# LCD_Button.net
KiCad netlist of a schematic drawn in Altium Designer
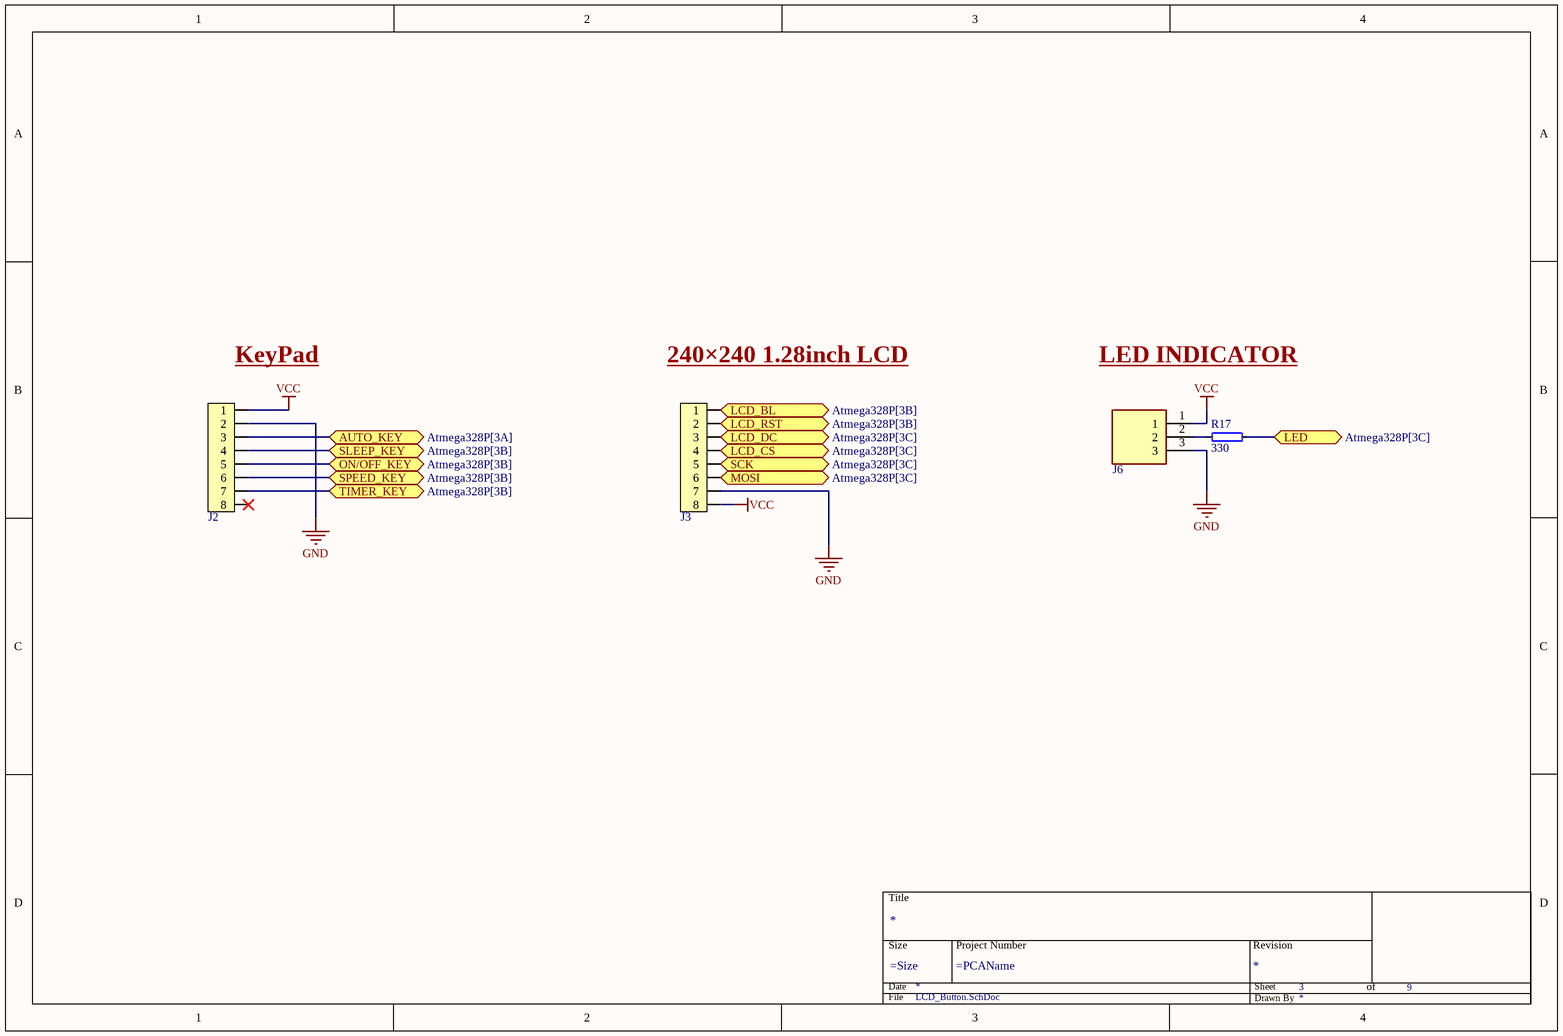
[diagram p0: LCD_Button.SchDoc]

(export (version "E")
  (design (tool "Eeschema 10.0.6"))
  (components
    (comp (ref "*") (value "Title Block") (libsource (lib "HEPA_LIB") (part "Title Block")))
    (comp (ref "J2")
      (value "8way Connector")
      (footprint "TE_640455-8")
      (description "6Way Right Angle JST-XH connector Male 2.54mm Pitch")
      (fields (field (name "PART NUMBER") "JST-XH") (field (name "PUBLISHER") "Metal Circuits"))
      (libsource (lib "HEPA_LIB") (part "JST 8Way"))
    )
    (comp (ref "J3")
      (value "8way Connector")
      (footprint "TE_640455-8")
      (description "6Way Right Angle JST-XH connector Male 2.54mm Pitch")
      (fields (field (name "PART NUMBER") "JST-XH") (field (name "PUBLISHER") "Metal Circuits"))
      (libsource (lib "HEPA_LIB") (part "JST 8Way"))
    )
    (comp (ref "J6")
      (value "CONN HEADER VERT 3POS 2.5MM")
      (footprint "JST_B3B-XH-A(LF)(SN)")
      (description "Connector Header Through Hole 3 position 0.098\" (2.50mm)")
      (fields
        (field (name "PART NUMBER") "B3B-XH-A(LF)(SN)")
        (field (name "MANUFACTURER") "JST Sales America Inc.")
        (field (name "PUBLISHER") "Metal Circuits")
      )
      (libsource (lib "Integrated_Library_Altium") (part "B3B-XH-A(LF)(SN)"))
    )
    (comp (ref "R17")
      (value "330")
      (footprint "RESC2012X65N")
      (description "RES SMD 1% 1/10W 0805")
      (fields (field (name "PART NUMBER") "RES_0805") (field (name "PUBLISHER") "Metal Circuits"))
      (libsource (lib "HEPA_LIB") (part "RES_0805"))
    )
  )
  (nets
    (net (code "1") (name "/AUTO_KEY") (class "Default")
      (node (ref "J2") (pin "3") (pinfunction "3_3") (pintype "passive"))
    )
    (net (code "2") (name "/LCD_BL") (class "Default")
      (node (ref "J3") (pin "1") (pinfunction "1_1") (pintype "passive"))
    )
    (net (code "3") (name "/LCD_CS") (class "Default")
      (node (ref "J3") (pin "4") (pinfunction "4_4") (pintype "passive"))
    )
    (net (code "4") (name "/LCD_DC") (class "Default")
      (node (ref "J3") (pin "3") (pinfunction "3_3") (pintype "passive"))
    )
    (net (code "5") (name "/LCD_RST") (class "Default")
      (node (ref "J3") (pin "2") (pinfunction "2_2") (pintype "passive"))
    )
    (net (code "6") (name "/LED") (class "Default")
      (node (ref "R17") (pin "1") (pinfunction "1_1") (pintype "passive"))
    )
    (net (code "7") (name "/MOSI") (class "Default")
      (node (ref "J3") (pin "6") (pinfunction "6_6") (pintype "passive"))
    )
    (net (code "8") (name "/ON{slash}OFF_KEY") (class "Default")
      (node (ref "J2") (pin "5") (pinfunction "5_5") (pintype "passive"))
    )
    (net (code "9") (name "/SCK") (class "Default")
      (node (ref "J3") (pin "5") (pinfunction "5_5") (pintype "passive"))
    )
    (net (code "10") (name "/SLEEP_KEY") (class "Default")
      (node (ref "J2") (pin "4") (pinfunction "4_4") (pintype "passive"))
    )
    (net (code "11") (name "/SPEED_KEY") (class "Default")
      (node (ref "J2") (pin "6") (pinfunction "6_6") (pintype "passive"))
    )
    (net (code "12") (name "/TIMER_KEY") (class "Default")
      (node (ref "J2") (pin "7") (pinfunction "7_7") (pintype "passive"))
    )
    (net (code "13") (name "GND") (class "Default")
      (node (ref "J2") (pin "2") (pinfunction "2_2") (pintype "passive"))
      (node (ref "J3") (pin "7") (pinfunction "7_7") (pintype "passive"))
      (node (ref "J6") (pin "3") (pinfunction "3_3") (pintype "passive"))
    )
    (net (code "14") (name "Net-(J6-Pad2)") (class "Default")
      (node (ref "J6") (pin "2") (pinfunction "2_2") (pintype "passive"))
      (node (ref "R17") (pin "2") (pinfunction "2_2") (pintype "passive"))
    )
    (net (code "15") (name "VCC") (class "Default")
      (node (ref "J2") (pin "1") (pinfunction "1_1") (pintype "passive"))
      (node (ref "J3") (pin "8") (pinfunction "8_8") (pintype "passive"))
      (node (ref "J6") (pin "1") (pinfunction "1_1") (pintype "passive"))
    )
    (net (code "16") (name "unconnected-(J2-Pad8)") (class "Default")
      (node (ref "J2") (pin "8") (pinfunction "8_8") (pintype "passive+no_connect"))
    )
  )
)
